# design.net
KiCad netlist of a schematic drawn in Altium Designer
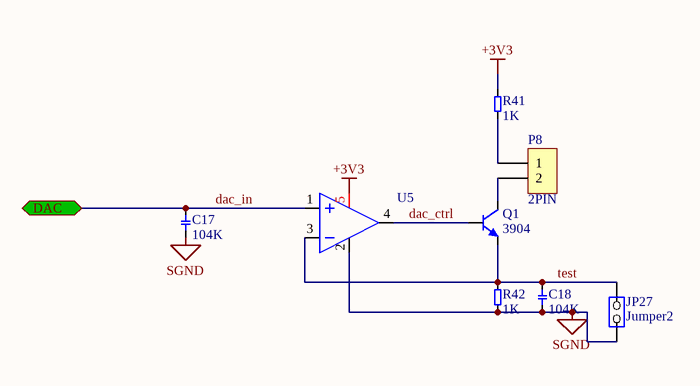
[diagram p0: 变送器.SchDoc]

(export (version "E")
  (design (tool "Eeschema 10.0.6"))
  (components
    (comp (ref "C17")
      (value "104K")
      (footprint "0603")
      (description "电容")
      (fields (field (name "PUBLISHER") "Altium Limited"))
      (libsource (lib "Miscellaneous Devices") (part "Cap"))
    )
    (comp (ref "C18")
      (value "104K")
      (footprint "0603")
      (description "电容")
      (fields (field (name "PUBLISHER") "Altium Limited"))
      (libsource (lib "Miscellaneous Devices") (part "Cap"))
    )
    (comp (ref "JP27")
      (value "Jumper2")
      (footprint "CON2-P2.54")
      (libsource (lib "Miscellaneous Connectors") (part "Jumper2"))
    )
    (comp (ref "P8")
      (value "2PIN")
      (footprint "CON2-P2.54")
      (description "连接器")
      (fields (field (name "PUBLISHER") "Altium Limited"))
      (libsource (lib "Miscellaneous Connectors") (part "Header 2"))
    )
    (comp (ref "Q1")
      (value "3904")
      (footprint "SOT-23-3L")
      (description "三极管")
      (fields (field (name "PUBLISHER") "Altium Limited"))
      (libsource (lib "Miscellaneous Devices") (part "transistor NPN"))
    )
    (comp (ref "R41")
      (value "1K")
      (footprint "1206")
      (description "电阻")
      (fields (field (name "PUBLISHER") "Altium Limited"))
      (libsource (lib "Miscellaneous Devices") (part "Res1"))
    )
    (comp (ref "R42")
      (value "1K")
      (footprint "1206")
      (description "电阻")
      (fields (field (name "PUBLISHER") "Altium Limited"))
      (libsource (lib "Miscellaneous Devices") (part "Res1"))
    )
    (comp (ref "U5")
      (value "LM321")
      (footprint "SOT-23-5L")
      (description "运放")
      (libsource (lib "Miscellaneous Devices") (part "LM321"))
    )
  )
  (nets
    (net (code "1") (name "+3V3") (class "Default")
      (node (ref "R41") (pin "2") (pinfunction "2_2") (pintype "passive"))
      (node (ref "U5") (pin "5") (pinfunction "V+_5") (pintype "power_in"))
    )
    (net (code "2") (name "/dac_ctrl") (class "Default")
      (node (ref "Q1") (pin "1") (pinfunction "B_1") (pintype "passive"))
      (node (ref "U5") (pin "4") (pinfunction "OUT1_4") (pintype "passive"))
    )
    (net (code "3") (name "/dac_in") (class "Default")
      (node (ref "C17") (pin "2") (pinfunction "2_2") (pintype "passive"))
      (node (ref "U5") (pin "1") (pinfunction "IN1+_1") (pintype "passive"))
    )
    (net (code "4") (name "/test") (class "Default")
      (node (ref "C18") (pin "2") (pinfunction "2_2") (pintype "passive"))
      (node (ref "JP27") (pin "1") (pinfunction "COMMON_1") (pintype "passive"))
      (node (ref "Q1") (pin "2") (pinfunction "E_2") (pintype "passive"))
      (node (ref "R42") (pin "2") (pinfunction "2_2") (pintype "passive"))
      (node (ref "U5") (pin "3") (pinfunction "IN1-_3") (pintype "passive"))
    )
    (net (code "5") (name "Net-(P8-Pad1)") (class "Default")
      (node (ref "P8") (pin "1") (pinfunction "1_1") (pintype "passive"))
      (node (ref "R41") (pin "1") (pinfunction "1_1") (pintype "passive"))
    )
    (net (code "6") (name "Net-(Q1-C)") (class "Default")
      (node (ref "P8") (pin "2") (pinfunction "2_2") (pintype "passive"))
      (node (ref "Q1") (pin "3") (pinfunction "C_3") (pintype "passive"))
    )
    (net (code "7") (name "SGND") (class "Default")
      (node (ref "C17") (pin "1") (pinfunction "1_1") (pintype "passive"))
      (node (ref "C18") (pin "1") (pinfunction "1_1") (pintype "passive"))
      (node (ref "JP27") (pin "2") (pinfunction "NO_2") (pintype "passive"))
      (node (ref "R42") (pin "1") (pinfunction "1_1") (pintype "passive"))
      (node (ref "U5") (pin "2") (pinfunction "V-_2") (pintype "power_in"))
    )
  )
)
